# VeggieIrrigation.net
KiCad netlist of a schematic drawn in Altium Designer
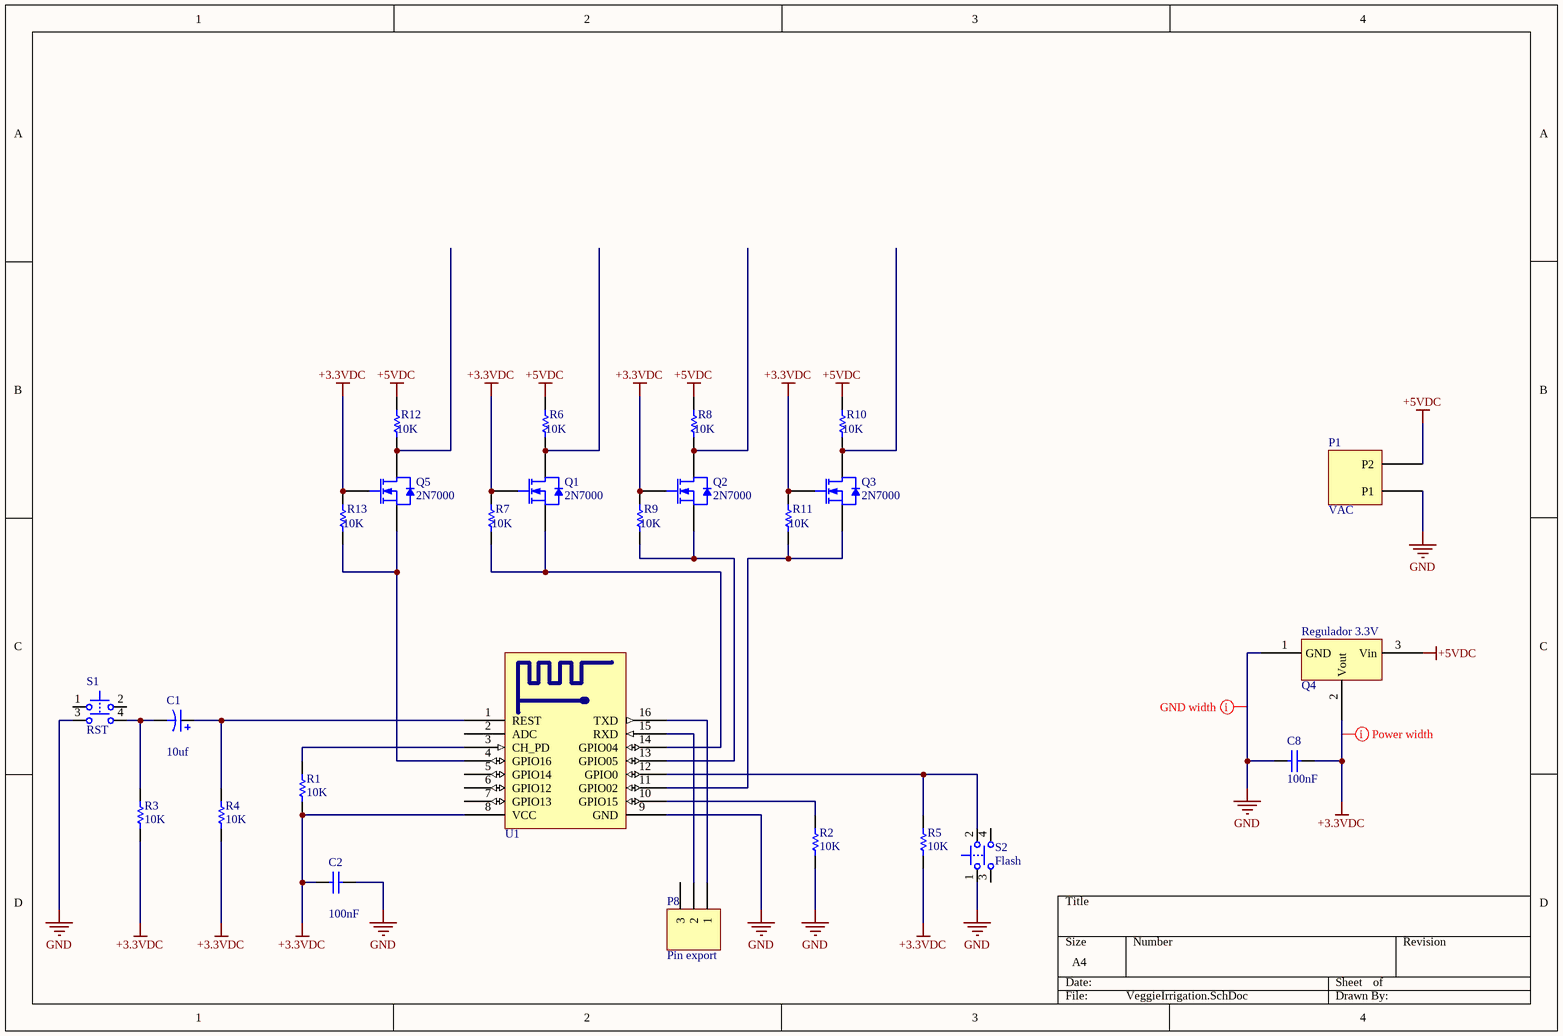
[diagram p0: VeggieIrrigation.SchDoc]

(export (version "E")
  (design (tool "Eeschema 10.0.6"))
  (components
    (comp (ref "C1")
      (value "10uf")
      (footprint "RAD-0.1")
      (description "Polarized Capacitor (Radial)")
      (fields (field (name "PUBLISHER") "Altium Limited"))
      (libsource (lib "Miscellaneous Devices") (part "Cap Pol1"))
    )
    (comp (ref "C2")
      (value "100nF")
      (footprint "RAD-0.1")
      (description "Capacitor")
      (fields (field (name "Comment") "100nf") (field (name "PUBLISHER") "Altium Limited"))
      (libsource (lib "Miscellaneous Devices") (part "Cap"))
    )
    (comp (ref "C8")
      (value "100nF")
      (footprint "RAD-0.1")
      (description "Capacitor")
      (fields (field (name "Comment") "100nf") (field (name "PUBLISHER") "Altium Limited"))
      (libsource (lib "Miscellaneous Devices") (part "Cap"))
    )
    (comp (ref "P1")
      (value "VAC")
      (footprint "ScrewTerminal-X2")
      (libsource (lib "ScrewTerminal_2X") (part "ScrewTerminal"))
    )
    (comp (ref "P8")
      (value "Pin export")
      (footprint "HDR1X3")
      (description "Header, 3-Pin")
      (fields (field (name "PUBLISHER") "Altium Limited"))
      (libsource (lib "Miscellaneous Connectors") (part "Header 3"))
    )
    (comp (ref "Q1")
      (value "2N7000")
      (footprint "SOT54")
      (description "N-channel Enhancement Mode Field-effect Transistor")
      (fields (field (name "PUBLISHER") "Altium Limited"))
      (libsource (lib "Philips Discrete MOSFET - Low Power") (part "2N7000"))
    )
    (comp (ref "Q2")
      (value "2N7000")
      (footprint "SOT54")
      (description "N-channel Enhancement Mode Field-effect Transistor")
      (fields (field (name "PUBLISHER") "Altium Limited"))
      (libsource (lib "Philips Discrete MOSFET - Low Power") (part "2N7000"))
    )
    (comp (ref "Q3")
      (value "2N7000")
      (footprint "SOT54")
      (description "N-channel Enhancement Mode Field-effect Transistor")
      (fields (field (name "PUBLISHER") "Altium Limited"))
      (libsource (lib "Philips Discrete MOSFET - Low Power") (part "2N7000"))
    )
    (comp (ref "Q4")
      (value "Regulador 3.3V")
      (footprint "TO-220-AB")
      (libsource (lib "AMS1117") (part "AMS1117"))
    )
    (comp (ref "Q5")
      (value "2N7000")
      (footprint "SOT54")
      (description "N-channel Enhancement Mode Field-effect Transistor")
      (fields (field (name "PUBLISHER") "Altium Limited"))
      (libsource (lib "Philips Discrete MOSFET - Low Power") (part "2N7000"))
    )
    (comp (ref "R1")
      (value "10K")
      (footprint "AXIAL-0.3")
      (description "Resistor")
      (fields (field (name "PUBLISHER") "Altium Limited"))
      (libsource (lib "Miscellaneous Devices") (part "Res1"))
    )
    (comp (ref "R2")
      (value "10K")
      (footprint "AXIAL-0.3")
      (description "Resistor")
      (fields (field (name "PUBLISHER") "Altium Limited"))
      (libsource (lib "Miscellaneous Devices") (part "Res1"))
    )
    (comp (ref "R3")
      (value "10K")
      (footprint "AXIAL-0.3")
      (description "Resistor")
      (fields (field (name "PUBLISHER") "Altium Limited"))
      (libsource (lib "Miscellaneous Devices") (part "Res1"))
    )
    (comp (ref "R4")
      (value "10K")
      (footprint "AXIAL-0.3")
      (description "Resistor")
      (fields (field (name "PUBLISHER") "Altium Limited"))
      (libsource (lib "Miscellaneous Devices") (part "Res1"))
    )
    (comp (ref "R5")
      (value "10K")
      (footprint "AXIAL-0.3")
      (description "Resistor")
      (fields (field (name "PUBLISHER") "Altium Limited"))
      (libsource (lib "Miscellaneous Devices") (part "Res1"))
    )
    (comp (ref "R6")
      (value "10K")
      (footprint "AXIAL-0.3")
      (description "Resistor")
      (fields (field (name "PUBLISHER") "Altium Limited"))
      (libsource (lib "Miscellaneous Devices") (part "Res1"))
    )
    (comp (ref "R7")
      (value "10K")
      (footprint "AXIAL-0.3")
      (description "Resistor")
      (fields (field (name "PUBLISHER") "Altium Limited"))
      (libsource (lib "Miscellaneous Devices") (part "Res1"))
    )
    (comp (ref "R8")
      (value "10K")
      (footprint "AXIAL-0.3")
      (description "Resistor")
      (fields (field (name "PUBLISHER") "Altium Limited"))
      (libsource (lib "Miscellaneous Devices") (part "Res1"))
    )
    (comp (ref "R9")
      (value "10K")
      (footprint "AXIAL-0.3")
      (description "Resistor")
      (fields (field (name "PUBLISHER") "Altium Limited"))
      (libsource (lib "Miscellaneous Devices") (part "Res1"))
    )
    (comp (ref "R10")
      (value "10K")
      (footprint "AXIAL-0.3")
      (description "Resistor")
      (fields (field (name "PUBLISHER") "Altium Limited"))
      (libsource (lib "Miscellaneous Devices") (part "Res1"))
    )
    (comp (ref "R11")
      (value "10K")
      (footprint "AXIAL-0.3")
      (description "Resistor")
      (fields (field (name "PUBLISHER") "Altium Limited"))
      (libsource (lib "Miscellaneous Devices") (part "Res1"))
    )
    (comp (ref "R12")
      (value "10K")
      (footprint "AXIAL-0.3")
      (description "Resistor")
      (fields (field (name "PUBLISHER") "Altium Limited"))
      (libsource (lib "Miscellaneous Devices") (part "Res1"))
    )
    (comp (ref "R13")
      (value "10K")
      (footprint "AXIAL-0.3")
      (description "Resistor")
      (fields (field (name "PUBLISHER") "Altium Limited"))
      (libsource (lib "Miscellaneous Devices") (part "Res1"))
    )
    (comp (ref "S1")
      (value "RST")
      (footprint "IT-2175")
      (description "Tactile Switch, DPST; Thru-Hole; Vertical; Rating DC 12V, 50mA (max)")
      (fields (field (name "PUBLISHER") "Altium Limited"))
      (libsource (lib "IL Switch Push Button") (part "IT-2175"))
    )
    (comp (ref "S2")
      (value "Flash")
      (footprint "IT-2175")
      (description "Tactile Switch, DPST; Thru-Hole; Vertical; Rating DC 12V, 50mA (max)")
      (fields (field (name "PUBLISHER") "Altium Limited"))
      (libsource (lib "IL Switch Push Button") (part "IT-2175"))
    )
    (comp (ref "U1") (value "ESP-12") (footprint "ESP_12") (libsource (lib "ESP-12") (part "ESP-12")))
  )
  (nets
    (net (code "1") (name "+3.3VDC") (class "Default")
      (node (ref "C2") (pin "1") (pinfunction "1_1") (pintype "passive"))
      (node (ref "C8") (pin "2") (pinfunction "2_2") (pintype "passive"))
      (node (ref "Q1") (pin "2") (pinfunction "G_2") (pintype "passive"))
      (node (ref "Q2") (pin "2") (pinfunction "G_2") (pintype "passive"))
      (node (ref "Q3") (pin "2") (pinfunction "G_2") (pintype "passive"))
      (node (ref "Q4") (pin "2") (pinfunction "Vout_2") (pintype "passive"))
      (node (ref "Q5") (pin "2") (pinfunction "G_2") (pintype "passive"))
      (node (ref "R1") (pin "1") (pinfunction "1_1") (pintype "passive"))
      (node (ref "R11") (pin "2") (pinfunction "2_2") (pintype "passive"))
      (node (ref "R13") (pin "2") (pinfunction "2_2") (pintype "passive"))
      (node (ref "R3") (pin "2") (pinfunction "2_2") (pintype "passive"))
      (node (ref "R4") (pin "2") (pinfunction "2_2") (pintype "passive"))
      (node (ref "R5") (pin "2") (pinfunction "2_2") (pintype "passive"))
      (node (ref "R7") (pin "2") (pinfunction "2_2") (pintype "passive"))
      (node (ref "R9") (pin "2") (pinfunction "2_2") (pintype "passive"))
      (node (ref "U1") (pin "8") (pinfunction "VCC_8") (pintype "power_in"))
    )
    (net (code "2") (name "+5VDC") (class "Default")
      (node (ref "P1") (pin "2") (pinfunction "P2_2") (pintype "passive"))
      (node (ref "Q4") (pin "3") (pinfunction "Vin_3") (pintype "passive"))
      (node (ref "R10") (pin "2") (pinfunction "2_2") (pintype "passive"))
      (node (ref "R12") (pin "2") (pinfunction "2_2") (pintype "passive"))
      (node (ref "R6") (pin "2") (pinfunction "2_2") (pintype "passive"))
      (node (ref "R8") (pin "2") (pinfunction "2_2") (pintype "passive"))
    )
    (net (code "3") (name "GND") (class "Default")
      (node (ref "C2") (pin "2") (pinfunction "2_2") (pintype "passive"))
      (node (ref "C8") (pin "1") (pinfunction "1_1") (pintype "passive"))
      (node (ref "P1") (pin "1") (pinfunction "P1_1") (pintype "passive"))
      (node (ref "Q4") (pin "1") (pinfunction "GND_1") (pintype "passive"))
      (node (ref "R2") (pin "2") (pinfunction "2_2") (pintype "passive"))
      (node (ref "S1") (pin "3") (pinfunction "3_3") (pintype "passive"))
      (node (ref "S2") (pin "1") (pinfunction "1_1") (pintype "passive"))
      (node (ref "U1") (pin "9") (pinfunction "GND_9") (pintype "power_in"))
    )
    (net (code "4") (name "Net-(C1-Pad2)") (class "Default")
      (node (ref "C1") (pin "2") (pinfunction "2_2") (pintype "passive"))
      (node (ref "R3") (pin "1") (pinfunction "1_1") (pintype "passive"))
      (node (ref "S1") (pin "4") (pinfunction "4_4") (pintype "passive"))
    )
    (net (code "5") (name "Net-(Q1-D)") (class "Default")
      (node (ref "Q1") (pin "1") (pinfunction "D_1") (pintype "passive"))
      (node (ref "R6") (pin "1") (pinfunction "1_1") (pintype "passive"))
    )
    (net (code "6") (name "Net-(Q1-S)") (class "Default")
      (node (ref "Q1") (pin "3") (pinfunction "S_3") (pintype "passive"))
      (node (ref "R7") (pin "1") (pinfunction "1_1") (pintype "passive"))
      (node (ref "U1") (pin "14") (pinfunction "GPIO04_14") (pintype "bidirectional"))
    )
    (net (code "7") (name "Net-(Q2-D)") (class "Default")
      (node (ref "Q2") (pin "1") (pinfunction "D_1") (pintype "passive"))
      (node (ref "R8") (pin "1") (pinfunction "1_1") (pintype "passive"))
    )
    (net (code "8") (name "Net-(Q2-S)") (class "Default")
      (node (ref "Q2") (pin "3") (pinfunction "S_3") (pintype "passive"))
      (node (ref "R9") (pin "1") (pinfunction "1_1") (pintype "passive"))
      (node (ref "U1") (pin "13") (pinfunction "GPIO05_13") (pintype "bidirectional"))
    )
    (net (code "9") (name "Net-(Q3-D)") (class "Default")
      (node (ref "Q3") (pin "1") (pinfunction "D_1") (pintype "passive"))
      (node (ref "R10") (pin "1") (pinfunction "1_1") (pintype "passive"))
    )
    (net (code "10") (name "Net-(Q3-S)") (class "Default")
      (node (ref "Q3") (pin "3") (pinfunction "S_3") (pintype "passive"))
      (node (ref "R11") (pin "1") (pinfunction "1_1") (pintype "passive"))
      (node (ref "U1") (pin "11") (pinfunction "GPIO02_11") (pintype "bidirectional"))
    )
    (net (code "11") (name "Net-(Q5-D)") (class "Default")
      (node (ref "Q5") (pin "1") (pinfunction "D_1") (pintype "passive"))
      (node (ref "R12") (pin "1") (pinfunction "1_1") (pintype "passive"))
    )
    (net (code "12") (name "Net-(Q5-S)") (class "Default")
      (node (ref "Q5") (pin "3") (pinfunction "S_3") (pintype "passive"))
      (node (ref "R13") (pin "1") (pinfunction "1_1") (pintype "passive"))
      (node (ref "U1") (pin "4") (pinfunction "GPIO16_4") (pintype "bidirectional"))
    )
    (net (code "13") (name "Net-(U1-CH_PD)") (class "Default")
      (node (ref "R1") (pin "2") (pinfunction "2_2") (pintype "passive"))
      (node (ref "U1") (pin "3") (pinfunction "CH_PD_3") (pintype "input"))
    )
    (net (code "14") (name "Net-(U1-GPIO0)") (class "Default")
      (node (ref "R5") (pin "1") (pinfunction "1_1") (pintype "passive"))
      (node (ref "S2") (pin "2") (pinfunction "2_2") (pintype "passive"))
      (node (ref "U1") (pin "12") (pinfunction "GPIO0_12") (pintype "bidirectional"))
    )
    (net (code "15") (name "Net-(U1-GPIO15)") (class "Default")
      (node (ref "R2") (pin "1") (pinfunction "1_1") (pintype "passive"))
      (node (ref "U1") (pin "10") (pinfunction "GPIO15_10") (pintype "bidirectional"))
    )
    (net (code "16") (name "Net-(U1-REST)") (class "Default")
      (node (ref "C1") (pin "1") (pinfunction "1_1") (pintype "passive"))
      (node (ref "R4") (pin "1") (pinfunction "1_1") (pintype "passive"))
      (node (ref "U1") (pin "1") (pinfunction "REST_1") (pintype "passive"))
    )
    (net (code "17") (name "Net-(U1-RXD)") (class "Default")
      (node (ref "P8") (pin "2") (pinfunction "2_2") (pintype "passive"))
      (node (ref "U1") (pin "15") (pinfunction "RXD_15") (pintype "input"))
    )
    (net (code "18") (name "Net-(U1-TXD)") (class "Default")
      (node (ref "P8") (pin "1") (pinfunction "1_1") (pintype "passive"))
      (node (ref "U1") (pin "16") (pinfunction "TXD_16") (pintype "output"))
    )
    (net (code "19") (name "unconnected-(P8-Pad3)") (class "Default")
      (node (ref "P8") (pin "3") (pinfunction "3_3") (pintype "passive"))
    )
    (net (code "20") (name "unconnected-(S1-Pad1)") (class "Default")
      (node (ref "S1") (pin "1") (pinfunction "1_1") (pintype "passive"))
    )
    (net (code "21") (name "unconnected-(S1-Pad2)") (class "Default")
      (node (ref "S1") (pin "2") (pinfunction "2_2") (pintype "passive"))
    )
    (net (code "22") (name "unconnected-(S2-Pad3)") (class "Default")
      (node (ref "S2") (pin "3") (pinfunction "3_3") (pintype "passive"))
    )
    (net (code "23") (name "unconnected-(S2-Pad4)") (class "Default")
      (node (ref "S2") (pin "4") (pinfunction "4_4") (pintype "passive"))
    )
    (net (code "24") (name "unconnected-(U1-ADC-Pad2)") (class "Default")
      (node (ref "U1") (pin "2") (pinfunction "ADC_2") (pintype "passive"))
    )
    (net (code "25") (name "unconnected-(U1-GPIO12-Pad6)") (class "Default")
      (node (ref "U1") (pin "6") (pinfunction "GPIO12_6") (pintype "bidirectional"))
    )
    (net (code "26") (name "unconnected-(U1-GPIO13-Pad7)") (class "Default")
      (node (ref "U1") (pin "7") (pinfunction "GPIO13_7") (pintype "bidirectional"))
    )
    (net (code "27") (name "unconnected-(U1-GPIO14-Pad5)") (class "Default")
      (node (ref "U1") (pin "5") (pinfunction "GPIO14_5") (pintype "bidirectional"))
    )
  )
)
